# receiver.net
KiCad netlist of a schematic drawn in EAGLE
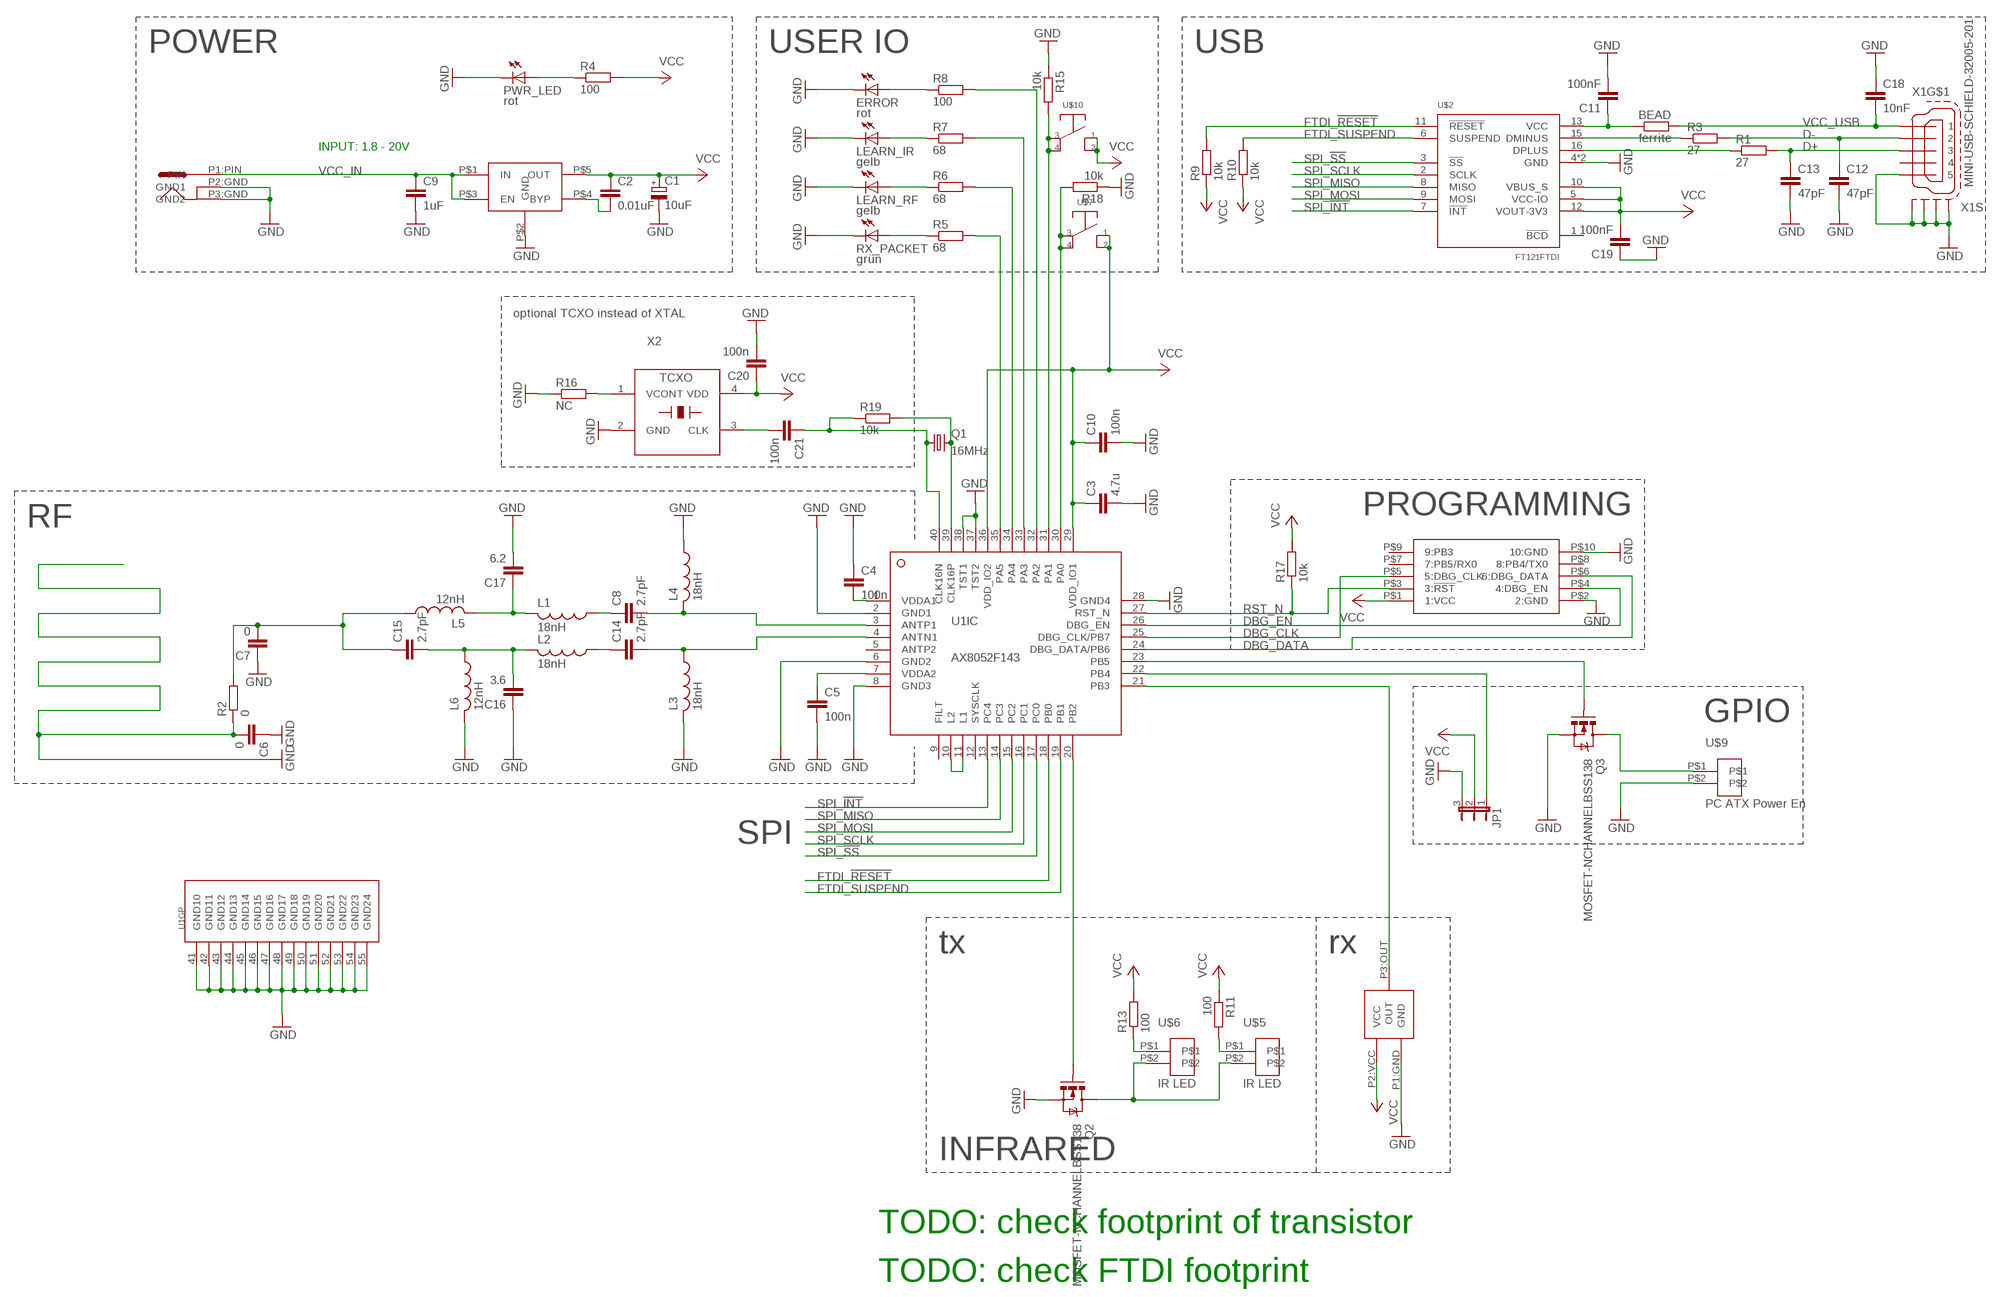
[diagram p0: schematic, sheet 1]

(export (version "E")
  (design (tool "Eeschema 10.0.6"))
  (components
    (comp (ref "BEAD")
      (value "ferrite")
      (footprint "eagle-import:R0603")
      (libsource (lib "eagle-import") (part "R-EU_R0603"))
    )
    (comp (ref "C1")
      (value "10uF")
      (footprint "eagle-import:153CLV-0405")
      (libsource (lib "eagle-import") (part "CPOL-EU153CLV-0405"))
    )
    (comp (ref "C2")
      (value "0.01uF")
      (footprint "eagle-import:C0603")
      (libsource (lib "eagle-import") (part "C-EUC0603"))
    )
    (comp (ref "C3")
      (value "4.7u")
      (footprint "eagle-import:C0805")
      (libsource (lib "eagle-import") (part "C-EUC0805"))
    )
    (comp (ref "C4")
      (value "100n")
      (footprint "eagle-import:C0603")
      (libsource (lib "eagle-import") (part "C-EUC0603"))
    )
    (comp (ref "C5")
      (value "100n")
      (footprint "eagle-import:C0603")
      (libsource (lib "eagle-import") (part "C-EUC0603"))
    )
    (comp (ref "C6")
      (value "0")
      (footprint "eagle-import:C0603")
      (libsource (lib "eagle-import") (part "C-EUC0603"))
    )
    (comp (ref "C7")
      (value "0")
      (footprint "eagle-import:C0603")
      (libsource (lib "eagle-import") (part "C-EUC0603"))
    )
    (comp (ref "C8")
      (value "2.7pF")
      (footprint "eagle-import:C0603")
      (libsource (lib "eagle-import") (part "C-EUC0603"))
    )
    (comp (ref "C9")
      (value "1uF")
      (footprint "eagle-import:C0805K")
      (libsource (lib "eagle-import") (part "C-EUC0805K"))
    )
    (comp (ref "C10")
      (value "100n")
      (footprint "eagle-import:C0603")
      (libsource (lib "eagle-import") (part "C-EUC0603"))
    )
    (comp (ref "C11")
      (value "100nF")
      (footprint "eagle-import:C0603K")
      (libsource (lib "eagle-import") (part "C-EUC0603K"))
    )
    (comp (ref "C12")
      (value "47pF")
      (footprint "eagle-import:C0603K")
      (libsource (lib "eagle-import") (part "C-EUC0603K"))
    )
    (comp (ref "C13")
      (value "47pF")
      (footprint "eagle-import:C0603K")
      (libsource (lib "eagle-import") (part "C-EUC0603K"))
    )
    (comp (ref "C14")
      (value "2.7pF")
      (footprint "eagle-import:C0603")
      (libsource (lib "eagle-import") (part "C-EUC0603"))
    )
    (comp (ref "C15")
      (value "2.7pF")
      (footprint "eagle-import:C0603")
      (libsource (lib "eagle-import") (part "C-EUC0603"))
    )
    (comp (ref "C16")
      (value "3.6")
      (footprint "eagle-import:C0603")
      (libsource (lib "eagle-import") (part "C-EUC0603"))
    )
    (comp (ref "C17")
      (value "6.2")
      (footprint "eagle-import:C0603")
      (libsource (lib "eagle-import") (part "C-EUC0603"))
    )
    (comp (ref "C18")
      (value "10nF")
      (footprint "eagle-import:C0603K")
      (libsource (lib "eagle-import") (part "C-EUC0603K"))
    )
    (comp (ref "C19")
      (value "100nF")
      (footprint "eagle-import:C0603K")
      (libsource (lib "eagle-import") (part "C-EUC0603K"))
    )
    (comp (ref "C20")
      (value "100n")
      (footprint "eagle-import:C0603")
      (libsource (lib "eagle-import") (part "C-EUC0603"))
    )
    (comp (ref "C21")
      (value "100n")
      (footprint "eagle-import:C0603")
      (libsource (lib "eagle-import") (part "C-EUC0603"))
    )
    (comp (ref "ERROR")
      (value "rot")
      (footprint "eagle-import:CHIPLED_1206")
      (libsource (lib "eagle-import") (part "LEDCHIPLED_1206"))
    )
    (comp (ref "JP1")
      (value "JP2E")
      (footprint "eagle-import:JP2")
      (libsource (lib "eagle-import") (part "JP2E"))
    )
    (comp (ref "L1")
      (value "18nH")
      (footprint "eagle-import:C0603")
      (libsource (lib "eagle-import") (part "L-US0603"))
    )
    (comp (ref "L2")
      (value "18nH")
      (footprint "eagle-import:C0603")
      (libsource (lib "eagle-import") (part "L-US0603"))
    )
    (comp (ref "L3")
      (value "18nH")
      (footprint "eagle-import:C0603")
      (libsource (lib "eagle-import") (part "L-US0603"))
    )
    (comp (ref "L4")
      (value "18nH")
      (footprint "eagle-import:C0603")
      (libsource (lib "eagle-import") (part "L-US0603"))
    )
    (comp (ref "L5")
      (value "12nH")
      (footprint "eagle-import:C0603")
      (libsource (lib "eagle-import") (part "L-US0603"))
    )
    (comp (ref "L6")
      (value "12nH")
      (footprint "eagle-import:C0603")
      (libsource (lib "eagle-import") (part "L-US0603"))
    )
    (comp (ref "LEARN_IR")
      (value "gelb")
      (footprint "eagle-import:CHIPLED_1206")
      (libsource (lib "eagle-import") (part "LEDCHIPLED_1206"))
    )
    (comp (ref "LEARN_RF")
      (value "gelb")
      (footprint "eagle-import:CHIPLED_1206")
      (libsource (lib "eagle-import") (part "LEDCHIPLED_1206"))
    )
    (comp (ref "PWR_LED")
      (value "rot")
      (footprint "eagle-import:CHIPLED_1206")
      (libsource (lib "eagle-import") (part "LEDCHIPLED_1206"))
    )
    (comp (ref "Q1")
      (value "16MHz")
      (footprint "eagle-import:SM49")
      (libsource (lib "eagle-import") (part "CRYSTALSM49"))
    )
    (comp (ref "Q2")
      (value "MOSFET-NCHANNELBSS138")
      (footprint "eagle-import:SOT23")
      (libsource (lib "eagle-import") (part "MOSFET-NCHANNELBSS138"))
    )
    (comp (ref "Q3")
      (value "MOSFET-NCHANNELBSS138")
      (footprint "eagle-import:SOT23")
      (libsource (lib "eagle-import") (part "MOSFET-NCHANNELBSS138"))
    )
    (comp (ref "R1")
      (value "27")
      (footprint "eagle-import:R0603")
      (libsource (lib "eagle-import") (part "R-EU_R0603"))
    )
    (comp (ref "R2")
      (value "0")
      (footprint "eagle-import:R0603")
      (libsource (lib "eagle-import") (part "R-EU_R0603"))
    )
    (comp (ref "R3")
      (value "27")
      (footprint "eagle-import:R0603")
      (libsource (lib "eagle-import") (part "R-EU_R0603"))
    )
    (comp (ref "R4")
      (value "100")
      (footprint "eagle-import:R0603")
      (libsource (lib "eagle-import") (part "R-EU_R0603"))
    )
    (comp (ref "R5")
      (value "68")
      (footprint "eagle-import:R0603")
      (libsource (lib "eagle-import") (part "R-EU_R0603"))
    )
    (comp (ref "R6")
      (value "68")
      (footprint "eagle-import:R0603")
      (libsource (lib "eagle-import") (part "R-EU_R0603"))
    )
    (comp (ref "R7")
      (value "68")
      (footprint "eagle-import:R0603")
      (libsource (lib "eagle-import") (part "R-EU_R0603"))
    )
    (comp (ref "R8")
      (value "100")
      (footprint "eagle-import:R0603")
      (libsource (lib "eagle-import") (part "R-EU_R0603"))
    )
    (comp (ref "R9")
      (value "10k")
      (footprint "eagle-import:R0603")
      (libsource (lib "eagle-import") (part "R-EU_R0603"))
    )
    (comp (ref "R10")
      (value "10k")
      (footprint "eagle-import:R0603")
      (libsource (lib "eagle-import") (part "R-EU_R0603"))
    )
    (comp (ref "R11")
      (value "100")
      (footprint "eagle-import:R0603")
      (libsource (lib "eagle-import") (part "R-EU_R0603"))
    )
    (comp (ref "R13")
      (value "100")
      (footprint "eagle-import:R0603")
      (libsource (lib "eagle-import") (part "R-EU_R0603"))
    )
    (comp (ref "R15")
      (value "10k")
      (footprint "eagle-import:R0603")
      (libsource (lib "eagle-import") (part "R-EU_R0603"))
    )
    (comp (ref "R16")
      (value "NC")
      (footprint "eagle-import:R0603")
      (libsource (lib "eagle-import") (part "R-EU_R0603"))
    )
    (comp (ref "R17")
      (value "10k")
      (footprint "eagle-import:R0603")
      (libsource (lib "eagle-import") (part "R-EU_R0603"))
    )
    (comp (ref "R18")
      (value "10k")
      (footprint "eagle-import:R0603")
      (libsource (lib "eagle-import") (part "R-EU_R0603"))
    )
    (comp (ref "R19")
      (value "10k")
      (footprint "eagle-import:R0603")
      (libsource (lib "eagle-import") (part "R-EU_R0603"))
    )
    (comp (ref "RX_PACKET")
      (value "grün")
      (footprint "eagle-import:CHIPLED_1206")
      (libsource (lib "eagle-import") (part "LEDCHIPLED_1206"))
    )
    (comp (ref "U$1")
      (value "LT1761")
      (footprint "eagle-import:TSOT-23")
      (libsource (lib "eagle-import") (part "LT1761"))
    )
    (comp (ref "U$2")
      (value "FT121FTDI")
      (footprint "eagle-import:TSSOP16-FTDI")
      (libsource (lib "eagle-import") (part "FT121FTDI"))
    )
    (comp (ref "U$3")
      (value "2X5PIN-CONNECTOR")
      (footprint "eagle-import:2X5PIN-CONNECTOR-SMD")
      (libsource (lib "eagle-import") (part "2X5PIN-CONNECTOR"))
    )
    (comp (ref "U$4")
      (value "POWER_JACK")
      (footprint "eagle-import:POWER_JACK_3.4_1")
      (libsource (lib "eagle-import") (part "POWER_JACK"))
    )
    (comp (ref "U$5")
      (value "IR LED")
      (footprint "eagle-import:2PIN_PINHEADER")
      (libsource (lib "eagle-import") (part "2PIN-CONNECTOR2.57RASTER"))
    )
    (comp (ref "U$6")
      (value "IR LED")
      (footprint "eagle-import:2PIN_PINHEADER")
      (libsource (lib "eagle-import") (part "2PIN-CONNECTOR2.57RASTER"))
    )
    (comp (ref "U$7")
      (value "SWITCHSMD")
      (footprint "eagle-import:TACTILE_SWITCH_FSM2JSMA")
      (libsource (lib "eagle-import") (part "SWITCHSMD"))
    )
    (comp (ref "U$8")
      (value "IR_RECEIVER")
      (footprint "eagle-import:TSOP1738_IR_RECV")
      (libsource (lib "eagle-import") (part "IR_RECEIVER"))
    )
    (comp (ref "U$9")
      (value "PC ATX Power En")
      (footprint "eagle-import:2PIN_PINHEADER")
      (libsource (lib "eagle-import") (part "2PIN-CONNECTOR2.57RASTER"))
    )
    (comp (ref "U$10")
      (value "SWITCHSMD")
      (footprint "eagle-import:TACTILE_SWITCH_FSM2JSMA")
      (libsource (lib "eagle-import") (part "SWITCHSMD"))
    )
    (comp (ref "U1")
      (value "AX8052F143HS")
      (footprint "eagle-import:QFN40-H")
      (libsource (lib "eagle-import") (part "AX8052F143HS"))
    )
    (comp (ref "X1")
      (value "MINI-USB-SCHIELD-32005-201")
      (footprint "eagle-import:32005-201")
      (libsource (lib "eagle-import") (part "MINI-USB-SCHIELD-32005-201"))
    )
    (comp (ref "X2")
      (value "TCXO3225")
      (footprint "eagle-import:X3225")
      (libsource (lib "eagle-import") (part "TCXO3225"))
    )
  )
  (nets
    (net (code "1") (name "/D+") (class "Default")
      (node (ref "C13") (pin "1") (pinfunction "1_1") (pintype "passive"))
      (node (ref "R1") (pin "2") (pinfunction "2_2") (pintype "passive"))
      (node (ref "X1") (pin "3") (pinfunction "3_3") (pintype "passive"))
    )
    (net (code "2") (name "/D-") (class "Default")
      (node (ref "C12") (pin "1") (pinfunction "1_1") (pintype "passive"))
      (node (ref "R3") (pin "2") (pinfunction "2_2") (pintype "passive"))
      (node (ref "X1") (pin "2") (pinfunction "2_2") (pintype "passive"))
    )
    (net (code "3") (name "/DBG_CLK") (class "Default")
      (node (ref "U$3") (pin "P$5") (pinfunction "5:DBG_CLK_P$5") (pintype "bidirectional"))
      (node (ref "U1") (pin "25") (pinfunction "DBG_CLK/PB7_25") (pintype "bidirectional"))
    )
    (net (code "4") (name "/DBG_DATA") (class "Default")
      (node (ref "U$3") (pin "P$6") (pinfunction "6:DBG_DATA_P$6") (pintype "bidirectional"))
      (node (ref "U1") (pin "24") (pinfunction "DBG_DATA/PB6_24") (pintype "bidirectional"))
    )
    (net (code "5") (name "/DBG_EN") (class "Default")
      (node (ref "U$3") (pin "P$4") (pinfunction "4:DBG_EN_P$4") (pintype "bidirectional"))
      (node (ref "U1") (pin "26") (pinfunction "DBG_EN_26") (pintype "input"))
    )
    (net (code "6") (name "/FTDI_SUSPEND") (class "Default")
      (node (ref "R10") (pin "2") (pinfunction "2_2") (pintype "passive"))
      (node (ref "U$2") (pin "6") (pinfunction "SUSPEND_6") (pintype "bidirectional"))
      (node (ref "U1") (pin "19") (pinfunction "PB1_19") (pintype "bidirectional"))
    )
    (net (code "7") (name "/FTDI_~{RESET}") (class "Default")
      (node (ref "R9") (pin "2") (pinfunction "2_2") (pintype "passive"))
      (node (ref "U$2") (pin "11") (pinfunction "~{RESET}_11") (pintype "input"))
      (node (ref "U1") (pin "18") (pinfunction "PB0_18") (pintype "bidirectional"))
    )
    (net (code "8") (name "/RST_N") (class "Default")
      (node (ref "R17") (pin "1") (pinfunction "1_1") (pintype "passive"))
      (node (ref "U$3") (pin "P$3") (pinfunction "3:~{RST}_P$3") (pintype "bidirectional"))
      (node (ref "U1") (pin "27") (pinfunction "RST_N_27") (pintype "input"))
    )
    (net (code "9") (name "/SPI_MISO") (class "Default")
      (node (ref "U$2") (pin "8") (pinfunction "MISO_8") (pintype "output"))
      (node (ref "U1") (pin "14") (pinfunction "PC3_14") (pintype "bidirectional"))
    )
    (net (code "10") (name "/SPI_MOSI") (class "Default")
      (node (ref "U$2") (pin "9") (pinfunction "MOSI_9") (pintype "input"))
      (node (ref "U1") (pin "15") (pinfunction "PC2_15") (pintype "bidirectional"))
    )
    (net (code "11") (name "/SPI_SCLK") (class "Default")
      (node (ref "U$2") (pin "2") (pinfunction "SCLK_2") (pintype "input"))
      (node (ref "U1") (pin "16") (pinfunction "PC1_16") (pintype "bidirectional"))
    )
    (net (code "12") (name "/SPI_~{INT}") (class "Default")
      (node (ref "U$2") (pin "7") (pinfunction "~{INT}_7") (pintype "bidirectional"))
      (node (ref "U1") (pin "13") (pinfunction "PC4_13") (pintype "bidirectional"))
    )
    (net (code "13") (name "/SPI_~{SS}") (class "Default")
      (node (ref "U$2") (pin "3") (pinfunction "~{SS}_3") (pintype "input"))
      (node (ref "U1") (pin "17") (pinfunction "PC0_17") (pintype "bidirectional"))
    )
    (net (code "14") (name "/VCC_IN") (class "Default")
      (node (ref "C9") (pin "1") (pinfunction "1_1") (pintype "passive"))
      (node (ref "U$1") (pin "P$1") (pinfunction "IN_P$1") (pintype "bidirectional"))
      (node (ref "U$1") (pin "P$3") (pinfunction "EN_P$3") (pintype "bidirectional"))
      (node (ref "U$4") (pin "P1:PIN") (pinfunction "PIN_P1:PIN") (pintype "bidirectional"))
    )
    (net (code "15") (name "/VCC_USB") (class "Default")
      (node (ref "BEAD") (pin "2") (pinfunction "2_2") (pintype "passive"))
      (node (ref "C18") (pin "2") (pinfunction "2_2") (pintype "passive"))
      (node (ref "X1") (pin "1") (pinfunction "1_1") (pintype "passive"))
    )
    (net (code "16") (name "GND") (class "Default")
      (node (ref "C1") (pin "-") (pinfunction "-_-") (pintype "passive"))
      (node (ref "C10") (pin "2") (pinfunction "2_2") (pintype "passive"))
      (node (ref "C11") (pin "2") (pinfunction "2_2") (pintype "passive"))
      (node (ref "C12") (pin "2") (pinfunction "2_2") (pintype "passive"))
      (node (ref "C13") (pin "2") (pinfunction "2_2") (pintype "passive"))
      (node (ref "C16") (pin "1") (pinfunction "1_1") (pintype "passive"))
      (node (ref "C17") (pin "2") (pinfunction "2_2") (pintype "passive"))
      (node (ref "C18") (pin "1") (pinfunction "1_1") (pintype "passive"))
      (node (ref "C19") (pin "1") (pinfunction "1_1") (pintype "passive"))
      (node (ref "C20") (pin "2") (pinfunction "2_2") (pintype "passive"))
      (node (ref "C3") (pin "2") (pinfunction "2_2") (pintype "passive"))
      (node (ref "C4") (pin "1") (pinfunction "1_1") (pintype "passive"))
      (node (ref "C5") (pin "2") (pinfunction "2_2") (pintype "passive"))
      (node (ref "C6") (pin "1") (pinfunction "1_1") (pintype "passive"))
      (node (ref "C6") (pin "2") (pinfunction "2_2") (pintype "passive"))
      (node (ref "C7") (pin "1") (pinfunction "1_1") (pintype "passive"))
      (node (ref "C9") (pin "2") (pinfunction "2_2") (pintype "passive"))
      (node (ref "ERROR") (pin "C") (pinfunction "C_C") (pintype "passive"))
      (node (ref "JP1") (pin "3") (pinfunction "3_3") (pintype "passive"))
      (node (ref "L3") (pin "2") (pinfunction "2_2") (pintype "passive"))
      (node (ref "L4") (pin "1") (pinfunction "1_1") (pintype "passive"))
      (node (ref "L6") (pin "2") (pinfunction "2_2") (pintype "passive"))
      (node (ref "LEARN_IR") (pin "C") (pinfunction "C_C") (pintype "passive"))
      (node (ref "LEARN_RF") (pin "C") (pinfunction "C_C") (pintype "passive"))
      (node (ref "PWR_LED") (pin "C") (pinfunction "C_C") (pintype "passive"))
      (node (ref "Q2") (pin "2") (pinfunction "S_2") (pintype "passive"))
      (node (ref "Q3") (pin "2") (pinfunction "S_2") (pintype "passive"))
      (node (ref "R15") (pin "1") (pinfunction "1_1") (pintype "passive"))
      (node (ref "R16") (pin "1") (pinfunction "1_1") (pintype "passive"))
      (node (ref "R18") (pin "1") (pinfunction "1_1") (pintype "passive"))
      (node (ref "R2") (pin "1") (pinfunction "1_1") (pintype "passive"))
      (node (ref "RX_PACKET") (pin "C") (pinfunction "C_C") (pintype "passive"))
      (node (ref "U$1") (pin "P$2") (pinfunction "GND_P$2") (pintype "bidirectional"))
      (node (ref "U$2") (pin "14") (pinfunction "GND_14") (pintype "power_in"))
      (node (ref "U$2") (pin "4") (pinfunction "GND_4") (pintype "power_in"))
      (node (ref "U$3") (pin "P$10") (pinfunction "10:GND_P$10") (pintype "bidirectional"))
      (node (ref "U$3") (pin "P$2") (pinfunction "2:GND_P$2") (pintype "bidirectional"))
      (node (ref "U$4") (pin "P2:GND") (pinfunction "GND1_P2:GND") (pintype "bidirectional"))
      (node (ref "U$4") (pin "P3:GND") (pinfunction "GND2_P3:GND") (pintype "bidirectional"))
      (node (ref "U$8") (pin "P1:GND") (pinfunction "GND_P1:GND") (pintype "bidirectional"))
      (node (ref "U$9") (pin "P$2") (pinfunction "P$2_P$2") (pintype "bidirectional"))
      (node (ref "U1") (pin "2") (pinfunction "GND1_2") (pintype "power_in"))
      (node (ref "U1") (pin "28") (pinfunction "GND4_28") (pintype "power_in"))
      (node (ref "U1") (pin "37") (pinfunction "TST2_37") (pintype "bidirectional"))
      (node (ref "U1") (pin "38") (pinfunction "TST1_38") (pintype "power_in"))
      (node (ref "U1") (pin "41") (pinfunction "GND10_41") (pintype "power_in"))
      (node (ref "U1") (pin "42") (pinfunction "GND11_42") (pintype "power_in"))
      (node (ref "U1") (pin "43") (pinfunction "GND12_43") (pintype "power_in"))
      (node (ref "U1") (pin "44") (pinfunction "GND13_44") (pintype "power_in"))
      (node (ref "U1") (pin "45") (pinfunction "GND14_45") (pintype "power_in"))
      (node (ref "U1") (pin "46") (pinfunction "GND15_46") (pintype "power_in"))
      (node (ref "U1") (pin "47") (pinfunction "GND16_47") (pintype "power_in"))
      (node (ref "U1") (pin "48") (pinfunction "GND17_48") (pintype "power_in"))
      (node (ref "U1") (pin "49") (pinfunction "GND18_49") (pintype "power_in"))
      (node (ref "U1") (pin "50") (pinfunction "GND19_50") (pintype "power_in"))
      (node (ref "U1") (pin "51") (pinfunction "GND20_51") (pintype "power_in"))
      (node (ref "U1") (pin "52") (pinfunction "GND21_52") (pintype "power_in"))
      (node (ref "U1") (pin "53") (pinfunction "GND22_53") (pintype "power_in"))
      (node (ref "U1") (pin "54") (pinfunction "GND23_54") (pintype "power_in"))
      (node (ref "U1") (pin "55") (pinfunction "GND24_55") (pintype "power_in"))
      (node (ref "U1") (pin "6") (pinfunction "GND2_6") (pintype "passive"))
      (node (ref "U1") (pin "8") (pinfunction "GND3_8") (pintype "power_in"))
      (node (ref "X1") (pin "5") (pinfunction "5_5") (pintype "passive"))
      (node (ref "X1") (pin "M1") (pinfunction "S1_M1") (pintype "passive"))
      (node (ref "X1") (pin "M2") (pinfunction "S2_M2") (pintype "passive"))
      (node (ref "X1") (pin "M3") (pinfunction "S3_M3") (pintype "passive"))
      (node (ref "X1") (pin "M4") (pinfunction "S4_M4") (pintype "passive"))
      (node (ref "X2") (pin "2") (pinfunction "GND_2") (pintype "power_in"))
    )
    (net (code "17") (name "Net-(C8-Pad1)") (class "Default")
      (node (ref "C8") (pin "1") (pinfunction "1_1") (pintype "passive"))
      (node (ref "L1") (pin "1") (pinfunction "1_1") (pintype "passive"))
    )
    (net (code "18") (name "Net-(C14-Pad1)") (class "Default")
      (node (ref "C14") (pin "1") (pinfunction "1_1") (pintype "passive"))
      (node (ref "L2") (pin "1") (pinfunction "1_1") (pintype "passive"))
    )
    (net (code "19") (name "Net-(C15-Pad1)") (class "Default")
      (node (ref "C15") (pin "1") (pinfunction "1_1") (pintype "passive"))
      (node (ref "C7") (pin "2") (pinfunction "2_2") (pintype "passive"))
      (node (ref "L5") (pin "1") (pinfunction "1_1") (pintype "passive"))
      (node (ref "R2") (pin "2") (pinfunction "2_2") (pintype "passive"))
    )
    (net (code "20") (name "Net-(C15-Pad2)") (class "Default")
      (node (ref "C15") (pin "2") (pinfunction "2_2") (pintype "passive"))
      (node (ref "C16") (pin "2") (pinfunction "2_2") (pintype "passive"))
      (node (ref "L2") (pin "2") (pinfunction "2_2") (pintype "passive"))
      (node (ref "L6") (pin "1") (pinfunction "1_1") (pintype "passive"))
    )
    (net (code "21") (name "Net-(C17-Pad1)") (class "Default")
      (node (ref "C17") (pin "1") (pinfunction "1_1") (pintype "passive"))
      (node (ref "L1") (pin "2") (pinfunction "2_2") (pintype "passive"))
      (node (ref "L5") (pin "2") (pinfunction "2_2") (pintype "passive"))
    )
    (net (code "22") (name "Net-(ERROR-PadA)") (class "Default")
      (node (ref "ERROR") (pin "A") (pinfunction "A_A") (pintype "passive"))
      (node (ref "R8") (pin "1") (pinfunction "1_1") (pintype "passive"))
    )
    (net (code "23") (name "Net-(LEARN_IR-PadA)") (class "Default")
      (node (ref "LEARN_IR") (pin "A") (pinfunction "A_A") (pintype "passive"))
      (node (ref "R7") (pin "1") (pinfunction "1_1") (pintype "passive"))
    )
    (net (code "24") (name "Net-(LEARN_RF-PadA)") (class "Default")
      (node (ref "LEARN_RF") (pin "A") (pinfunction "A_A") (pintype "passive"))
      (node (ref "R6") (pin "1") (pinfunction "1_1") (pintype "passive"))
    )
    (net (code "25") (name "Net-(PWR_LED-PadA)") (class "Default")
      (node (ref "PWR_LED") (pin "A") (pinfunction "A_A") (pintype "passive"))
      (node (ref "R4") (pin "1") (pinfunction "1_1") (pintype "passive"))
    )
    (net (code "26") (name "Net-(Q2-D)") (class "Default")
      (node (ref "Q2") (pin "3") (pinfunction "D_3") (pintype "passive"))
      (node (ref "U$5") (pin "P$2") (pinfunction "P$2_P$2") (pintype "bidirectional"))
      (node (ref "U$6") (pin "P$2") (pinfunction "P$2_P$2") (pintype "bidirectional"))
    )
    (net (code "27") (name "Net-(Q2-G)") (class "Default")
      (node (ref "Q2") (pin "1") (pinfunction "G_1") (pintype "passive"))
      (node (ref "U1") (pin "20") (pinfunction "PB2_20") (pintype "bidirectional"))
    )
    (net (code "28") (name "Net-(Q3-D)") (class "Default")
      (node (ref "Q3") (pin "3") (pinfunction "D_3") (pintype "passive"))
      (node (ref "U$9") (pin "P$1") (pinfunction "P$1_P$1") (pintype "bidirectional"))
    )
    (net (code "29") (name "Net-(Q3-G)") (class "Default")
      (node (ref "Q3") (pin "1") (pinfunction "G_1") (pintype "passive"))
      (node (ref "U1") (pin "23") (pinfunction "PB5_23") (pintype "bidirectional"))
    )
    (net (code "30") (name "Net-(R5-Pad1)") (class "Default")
      (node (ref "R5") (pin "1") (pinfunction "1_1") (pintype "passive"))
      (node (ref "RX_PACKET") (pin "A") (pinfunction "A_A") (pintype "passive"))
    )
    (net (code "31") (name "Net-(R11-Pad2)") (class "Default")
      (node (ref "R11") (pin "2") (pinfunction "2_2") (pintype "passive"))
      (node (ref "U$5") (pin "P$1") (pinfunction "P$1_P$1") (pintype "bidirectional"))
    )
    (net (code "32") (name "Net-(R13-Pad1)") (class "Default")
      (node (ref "R13") (pin "1") (pinfunction "1_1") (pintype "passive"))
      (node (ref "U$6") (pin "P$1") (pinfunction "P$1_P$1") (pintype "bidirectional"))
    )
    (net (code "33") (name "Net-(U$1-BYP)") (class "Default")
      (node (ref "C2") (pin "2") (pinfunction "2_2") (pintype "passive"))
      (node (ref "U$1") (pin "P$4") (pinfunction "BYP_P$4") (pintype "bidirectional"))
    )
    (net (code "34") (name "Net-(U$2-DMINUS)") (class "Default")
      (node (ref "R3") (pin "1") (pinfunction "1_1") (pintype "passive"))
      (node (ref "U$2") (pin "15") (pinfunction "DMINUS_15") (pintype "bidirectional"))
    )
    (net (code "35") (name "Net-(U$2-DPLUS)") (class "Default")
      (node (ref "R1") (pin "1") (pinfunction "1_1") (pintype "passive"))
      (node (ref "U$2") (pin "16") (pinfunction "DPLUS_16") (pintype "bidirectional"))
    )
    (net (code "36") (name "Net-(U$2-VCC)") (class "Default")
      (node (ref "BEAD") (pin "1") (pinfunction "1_1") (pintype "passive"))
      (node (ref "C11") (pin "1") (pinfunction "1_1") (pintype "passive"))
      (node (ref "U$2") (pin "13") (pinfunction "VCC_13") (pintype "power_in"))
    )
    (net (code "37") (name "Net-(U$8-OUT)") (class "Default")
      (node (ref "U$8") (pin "P3:OUT") (pinfunction "OUT_P3:OUT") (pintype "bidirectional"))
      (node (ref "U1") (pin "21") (pinfunction "PB3_21") (pintype "bidirectional"))
    )
    (net (code "38") (name "Net-(U1B-ANTN1)") (class "Default")
      (node (ref "C14") (pin "2") (pinfunction "2_2") (pintype "passive"))
      (node (ref "L3") (pin "1") (pinfunction "1_1") (pintype "passive"))
      (node (ref "U1") (pin "4") (pinfunction "ANTN1_4") (pintype "power_in"))
    )
    (net (code "39") (name "Net-(U1B-ANTP1)") (class "Default")
      (node (ref "C8") (pin "2") (pinfunction "2_2") (pintype "passive"))
      (node (ref "L4") (pin "2") (pinfunction "2_2") (pintype "passive"))
      (node (ref "U1") (pin "3") (pinfunction "ANTP1_3") (pintype "power_in"))
    )
    (net (code "40") (name "Net-(U1B-CLK16N)") (class "Default")
      (node (ref "C21") (pin "1") (pinfunction "1_1") (pintype "passive"))
      (node (ref "Q1") (pin "1") (pinfunction "1_1") (pintype "passive"))
      (node (ref "R19") (pin "1") (pinfunction "1_1") (pintype "passive"))
      (node (ref "U1") (pin "40") (pinfunction "CLK16N_40") (pintype "passive"))
    )
    (net (code "41") (name "Net-(U1B-CLK16P)") (class "Default")
      (node (ref "Q1") (pin "2") (pinfunction "2_2") (pintype "passive"))
      (node (ref "R19") (pin "2") (pinfunction "2_2") (pintype "passive"))
      (node (ref "U1") (pin "39") (pinfunction "CLK16P_39") (pintype "passive"))
    )
    (net (code "42") (name "Net-(U1B-L1)") (class "Default")
      (node (ref "U1") (pin "10") (pinfunction "L2_10") (pintype "passive"))
      (node (ref "U1") (pin "11") (pinfunction "L1_11") (pintype "input"))
    )
    (net (code "43") (name "Net-(U1B-PA0)") (class "Default")
      (node (ref "R18") (pin "2") (pinfunction "2_2") (pintype "passive"))
      (node (ref "U$7") (pin "P3") (pinfunction "P3_P3") (pintype "bidirectional"))
      (node (ref "U$7") (pin "P4") (pinfunction "P4_P4") (pintype "bidirectional"))
      (node (ref "U1") (pin "30") (pinfunction "PA0_30") (pintype "bidirectional"))
    )
    (net (code "44") (name "Net-(U1B-PA1)") (class "Default")
      (node (ref "R15") (pin "2") (pinfunction "2_2") (pintype "passive"))
      (node (ref "U$10") (pin "P3") (pinfunction "P3_P3") (pintype "bidirectional"))
      (node (ref "U$10") (pin "P4") (pinfunction "P4_P4") (pintype "bidirectional"))
      (node (ref "U1") (pin "31") (pinfunction "PA1_31") (pintype "bidirectional"))
    )
    (net (code "45") (name "Net-(U1B-PA2)") (class "Default")
      (node (ref "R8") (pin "2") (pinfunction "2_2") (pintype "passive"))
      (node (ref "U1") (pin "32") (pinfunction "PA2_32") (pintype "bidirectional"))
    )
    (net (code "46") (name "Net-(U1B-PA3)") (class "Default")
      (node (ref "R7") (pin "2") (pinfunction "2_2") (pintype "passive"))
      (node (ref "U1") (pin "33") (pinfunction "PA3_33") (pintype "bidirectional"))
    )
    (net (code "47") (name "Net-(U1B-PA4)") (class "Default")
      (node (ref "R6") (pin "2") (pinfunction "2_2") (pintype "passive"))
      (node (ref "U1") (pin "34") (pinfunction "PA4_34") (pintype "bidirectional"))
    )
    (net (code "48") (name "Net-(U1B-PA5)") (class "Default")
      (node (ref "R5") (pin "2") (pinfunction "2_2") (pintype "passive"))
      (node (ref "U1") (pin "35") (pinfunction "PA5_35") (pintype "bidirectional"))
    )
    (net (code "49") (name "Net-(U1B-PB4)") (class "Default")
      (node (ref "JP1") (pin "1") (pinfunction "1_1") (pintype "passive"))
      (node (ref "U1") (pin "22") (pinfunction "PB4_22") (pintype "bidirectional"))
    )
    (net (code "50") (name "Net-(U1B-VDDA1)") (class "Default")
      (node (ref "C4") (pin "2") (pinfunction "2_2") (pintype "passive"))
      (node (ref "U1") (pin "1") (pinfunction "VDDA1_1") (pintype "power_in"))
    )
    (net (code "51") (name "Net-(U1B-VDDA2)") (class "Default")
      (node (ref "C5") (pin "1") (pinfunction "1_1") (pintype "passive"))
      (node (ref "U1") (pin "7") (pinfunction "VDDA2_7") (pintype "power_in"))
    )
    (net (code "52") (name "Net-(X2-CLK)") (class "Default")
      (node (ref "C21") (pin "2") (pinfunction "2_2") (pintype "passive"))
      (node (ref "X2") (pin "3") (pinfunction "CLK_3") (pintype "output"))
    )
    (net (code "53") (name "Net-(X2-VCONT)") (class "Default")
      (node (ref "R16") (pin "2") (pinfunction "2_2") (pintype "passive"))
      (node (ref "X2") (pin "1") (pinfunction "VCONT_1") (pintype "bidirectional"))
    )
    (net (code "54") (name "VCC") (class "Default")
      (node (ref "C1") (pin "+") (pinfunction "+_+") (pintype "passive"))
      (node (ref "C10") (pin "1") (pinfunction "1_1") (pintype "passive"))
      (node (ref "C19") (pin "2") (pinfunction "2_2") (pintype "passive"))
      (node (ref "C2") (pin "1") (pinfunction "1_1") (pintype "passive"))
      (node (ref "C20") (pin "1") (pinfunction "1_1") (pintype "passive"))
      (node (ref "C3") (pin "1") (pinfunction "1_1") (pintype "passive"))
      (node (ref "JP1") (pin "2") (pinfunction "2_2") (pintype "passive"))
      (node (ref "R10") (pin "1") (pinfunction "1_1") (pintype "passive"))
      (node (ref "R11") (pin "1") (pinfunction "1_1") (pintype "passive"))
      (node (ref "R13") (pin "2") (pinfunction "2_2") (pintype "passive"))
      (node (ref "R17") (pin "2") (pinfunction "2_2") (pintype "passive"))
      (node (ref "R4") (pin "2") (pinfunction "2_2") (pintype "passive"))
      (node (ref "R9") (pin "1") (pinfunction "1_1") (pintype "passive"))
      (node (ref "U$1") (pin "P$5") (pinfunction "OUT_P$5") (pintype "bidirectional"))
      (node (ref "U$10") (pin "P1") (pinfunction "P1_P1") (pintype "bidirectional"))
      (node (ref "U$10") (pin "P2") (pinfunction "P2_P2") (pintype "bidirectional"))
      (node (ref "U$2") (pin "10") (pinfunction "VBUS_S_10") (pintype "input"))
      (node (ref "U$2") (pin "12") (pinfunction "VOUT-3V3_12") (pintype "power_in"))
      (node (ref "U$2") (pin "5") (pinfunction "VCC-IO_5") (pintype "power_in"))
      (node (ref "U$3") (pin "P$1") (pinfunction "1:VCC_P$1") (pintype "bidirectional"))
      (node (ref "U$7") (pin "P1") (pinfunction "P1_P1") (pintype "bidirectional"))
      (node (ref "U$7") (pin "P2") (pinfunction "P2_P2") (pintype "bidirectional"))
      (node (ref "U$8") (pin "P2:VCC") (pinfunction "VCC_P2:VCC") (pintype "bidirectional"))
      (node (ref "U1") (pin "29") (pinfunction "VDD_IO1_29") (pintype "power_in"))
      (node (ref "U1") (pin "36") (pinfunction "VDD_IO2_36") (pintype "bidirectional"))
      (node (ref "X2") (pin "4") (pinfunction "VDD_4") (pintype "power_in"))
    )
    (net (code "55") (name "unconnected-(U$2-~{BCD}-Pad1)") (class "Default")
      (node (ref "U$2") (pin "1") (pinfunction "~{BCD}_1") (pintype "open_collector"))
    )
    (net (code "56") (name "unconnected-(U$3-7:PB5{slash}RX0-PadP$7)") (class "Default")
      (node (ref "U$3") (pin "P$7") (pinfunction "7:PB5/RX0_P$7") (pintype "bidirectional"))
    )
    (net (code "57") (name "unconnected-(U$3-8:PB4{slash}TX0-PadP$8)") (class "Default")
      (node (ref "U$3") (pin "P$8") (pinfunction "8:PB4/TX0_P$8") (pintype "bidirectional"))
    )
    (net (code "58") (name "unconnected-(U$3-9:PB3-PadP$9)") (class "Default")
      (node (ref "U$3") (pin "P$9") (pinfunction "9:PB3_P$9") (pintype "bidirectional"))
    )
    (net (code "59") (name "unconnected-(U1B-ANTP2-Pad5)") (class "Default")
      (node (ref "U1") (pin "5") (pinfunction "ANTP2_5") (pintype "passive"))
    )
    (net (code "60") (name "unconnected-(U1B-FILT-Pad9)") (class "Default")
      (node (ref "U1") (pin "9") (pinfunction "FILT_9") (pintype "passive"))
    )
    (net (code "61") (name "unconnected-(U1B-SYSCLK-Pad12)") (class "Default")
      (node (ref "U1") (pin "12") (pinfunction "SYSCLK_12") (pintype "output"))
    )
    (net (code "62") (name "unconnected-(X1-Pad4)") (class "Default")
      (node (ref "X1") (pin "4") (pinfunction "4_4") (pintype "passive"))
    )
  )
)
